# mp28164-buck-boost-flashlight-driver-17m.net
KiCad netlist of a schematic drawn in EAGLE
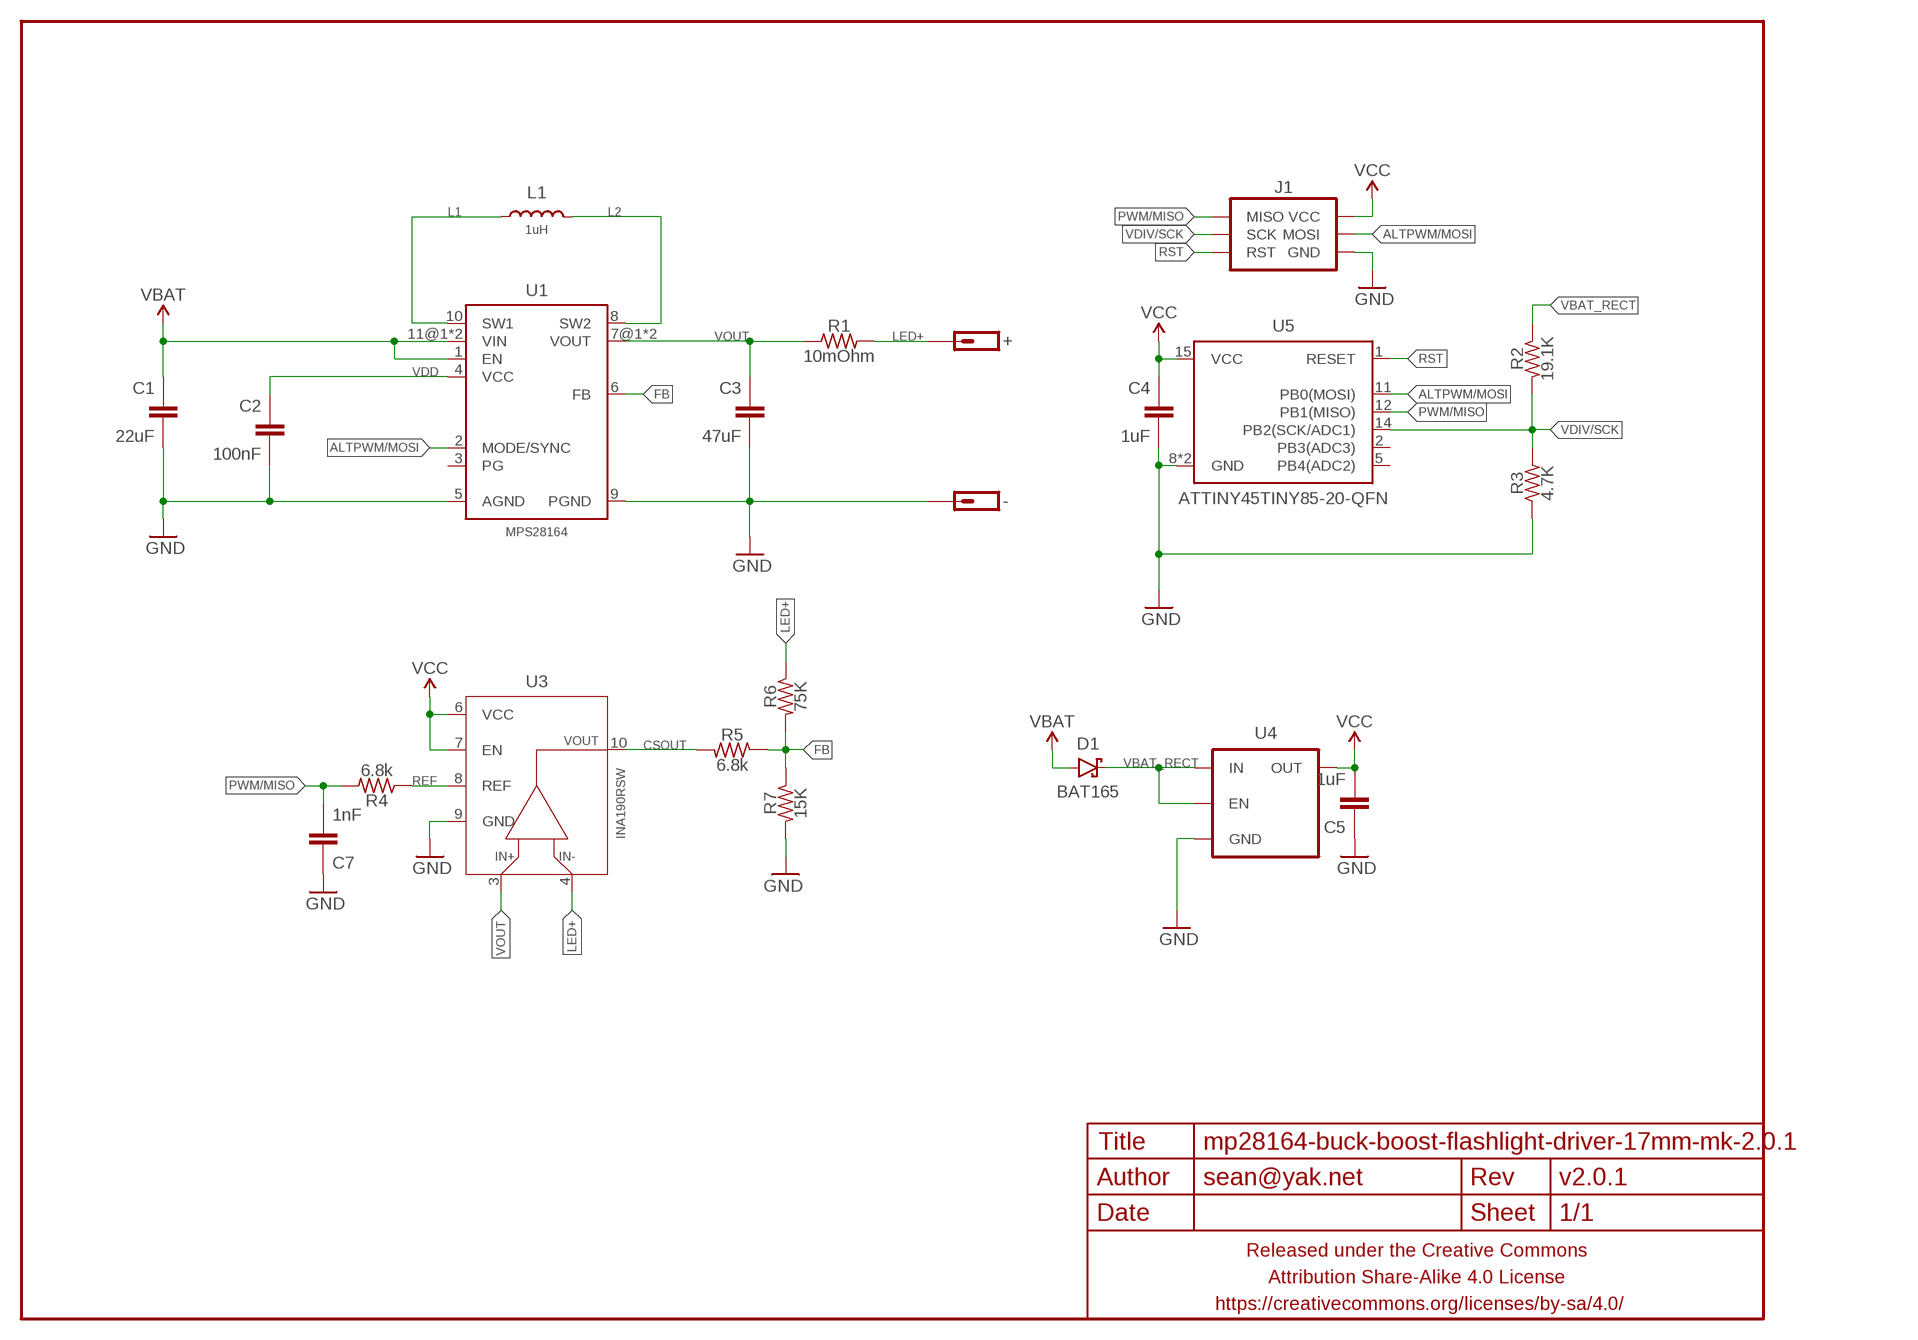
[diagram p0: schematic, sheet 1]

(export (version "E")
  (design (tool "Eeschema 10.0.6"))
  (components
    (comp (ref "+")
      (value "M01SMD-1.6MMX3.2MM-NS")
      (footprint "eagle-import:1X01-SMD-1.6MMX3.2MM-NS")
      (libsource (lib "eagle-import") (part "M01SMD-1.6MMX3.2MM-NS"))
    )
    (comp (ref "-")
      (value "M01SMD-1.6MMX3.2MM-NS")
      (footprint "eagle-import:1X01-SMD-1.6MMX3.2MM-NS")
      (libsource (lib "eagle-import") (part "M01SMD-1.6MMX3.2MM-NS"))
    )
    (comp (ref "C1")
      (value "22uF")
      (footprint "eagle-import:C1206")
      (libsource (lib "eagle-import") (part "CAPACITOR-CERAMICC1206"))
    )
    (comp (ref "C2")
      (value "100nF")
      (footprint "eagle-import:C0402")
      (libsource (lib "eagle-import") (part "CAPACITOR-CERAMICC0402"))
    )
    (comp (ref "C3")
      (value "47uF")
      (footprint "eagle-import:C1206")
      (libsource (lib "eagle-import") (part "CAPACITOR-CERAMICC1206"))
    )
    (comp (ref "C4")
      (value "1uF")
      (footprint "eagle-import:C0402")
      (libsource (lib "eagle-import") (part "CAPACITOR-CERAMICC0402"))
    )
    (comp (ref "C5")
      (value "1uF")
      (footprint "eagle-import:C0402")
      (libsource (lib "eagle-import") (part "CAPACITOR-CERAMICC0402"))
    )
    (comp (ref "C7")
      (value "1nF")
      (footprint "eagle-import:C0402")
      (libsource (lib "eagle-import") (part "CAPACITOR-CERAMICC0402"))
    )
    (comp (ref "D1")
      (value "BAT165")
      (footprint "eagle-import:SOD323-SCHOTTKY")
      (libsource (lib "eagle-import") (part "DIODE-SCHOTTKYSOD323"))
    )
    (comp (ref "FRAME1")
      (value "FRAME-LETTERNO_PACKAGE")
      (footprint "eagle-import:DUMMY")
      (fields
        (field (name "DESIGNER") "sean@yak.net")
        (field (name "VERSION") "v2.0.1")
        (field (name "DESIGNER_1") "sean@yak.net")
        (field (name "VERSION_1") "v2.0.1")
      )
      (libsource (lib "eagle-import") (part "FRAME-LETTERNO_PACKAGE"))
    )
    (comp (ref "J1")
      (value "AVR_SPI_PRG_6SMD-1.27MM")
      (footprint "eagle-import:2X3-1.27MM-SMD")
      (libsource (lib "eagle-import") (part "AVR_SPI_PRG_6SMD-1.27MM"))
    )
    (comp (ref "L1")
      (value "1uH")
      (footprint "eagle-import:XAL7070")
      (libsource (lib "eagle-import") (part "INDUCTORXAL7070"))
    )
    (comp (ref "R1")
      (value "10mOhm")
      (footprint "eagle-import:R1206")
      (libsource (lib "eagle-import") (part "RESISTORR1206"))
    )
    (comp (ref "R2")
      (value "19.1K")
      (footprint "eagle-import:R0402")
      (libsource (lib "eagle-import") (part "RESISTORR0402"))
    )
    (comp (ref "R3")
      (value "4.7K")
      (footprint "eagle-import:R0402")
      (libsource (lib "eagle-import") (part "RESISTORR0402"))
    )
    (comp (ref "R4")
      (value "6.8k")
      (footprint "eagle-import:R0402")
      (libsource (lib "eagle-import") (part "RESISTORR0402"))
    )
    (comp (ref "R5")
      (value "6.8k")
      (footprint "eagle-import:R0402")
      (libsource (lib "eagle-import") (part "RESISTORR0402"))
    )
    (comp (ref "R6")
      (value "75K")
      (footprint "eagle-import:R0402")
      (libsource (lib "eagle-import") (part "RESISTORR0402"))
    )
    (comp (ref "R7")
      (value "15K")
      (footprint "eagle-import:R0402")
      (libsource (lib "eagle-import") (part "RESISTORR0402"))
    )
    (comp (ref "U1")
      (value "MPS28164")
      (footprint "eagle-import:MPS28164")
      (libsource (lib "eagle-import") (part "MPS28164"))
    )
    (comp (ref "U3")
      (value "INA190RSW")
      (footprint "eagle-import:UQFN-10")
      (libsource (lib "eagle-import") (part "INA190RSW"))
    )
    (comp (ref "U4")
      (value "V_REG_ENTLV700")
      (footprint "eagle-import:SC70")
      (libsource (lib "eagle-import") (part "V_REG_ENTLV700"))
    )
    (comp (ref "U5")
      (value "ATTINY45TINY85-20-QFN")
      (footprint "eagle-import:QFN20")
      (libsource (lib "eagle-import") (part "ATTINY45TINY85-20-QFN"))
    )
  )
  (nets
    (net (code "1") (name "/CSOUT") (class "Default")
      (node (ref "R5") (pin "2") (pinfunction "2_2") (pintype "passive"))
      (node (ref "U3") (pin "10") (pinfunction "OUT_10") (pintype "bidirectional"))
    )
    (net (code "2") (name "/L1") (class "Default")
      (node (ref "L1") (pin "P$1") (pinfunction "1_P$1") (pintype "passive"))
      (node (ref "U1") (pin "10") (pinfunction "SW1_10") (pintype "bidirectional"))
    )
    (net (code "3") (name "/L2") (class "Default")
      (node (ref "L1") (pin "P$2") (pinfunction "2_P$2") (pintype "passive"))
      (node (ref "U1") (pin "8") (pinfunction "SW2_8") (pintype "bidirectional"))
    )
    (net (code "4") (name "/REF") (class "Default")
      (node (ref "R4") (pin "1") (pinfunction "1_1") (pintype "passive"))
      (node (ref "U3") (pin "8") (pinfunction "REF_8") (pintype "bidirectional"))
    )
    (net (code "5") (name "/VDD") (class "Default")
      (node (ref "C2") (pin "1") (pinfunction "1_1") (pintype "passive"))
      (node (ref "U1") (pin "4") (pinfunction "VCC_4") (pintype "bidirectional"))
    )
    (net (code "6") (name "ALTPWM{slash}MOSI") (class "Default")
      (node (ref "J1") (pin "4") (pinfunction "MOSI_4") (pintype "passive"))
      (node (ref "U1") (pin "2") (pinfunction "MODE/SYNC_2") (pintype "bidirectional"))
      (node (ref "U5") (pin "11") (pinfunction "PB0(MOSI)_11") (pintype "bidirectional"))
    )
    (net (code "7") (name "FB") (class "Default")
      (node (ref "R5") (pin "1") (pinfunction "1_1") (pintype "passive"))
      (node (ref "R6") (pin "2") (pinfunction "2_2") (pintype "passive"))
      (node (ref "R7") (pin "1") (pinfunction "1_1") (pintype "passive"))
      (node (ref "U1") (pin "6") (pinfunction "FB_6") (pintype "bidirectional"))
    )
    (net (code "8") (name "GND") (class "Default")
      (node (ref "-") (pin "P$1") (pinfunction "1_P$1") (pintype "passive"))
      (node (ref "C1") (pin "2") (pinfunction "2_2") (pintype "passive"))
      (node (ref "C2") (pin "2") (pinfunction "2_2") (pintype "passive"))
      (node (ref "C3") (pin "2") (pinfunction "2_2") (pintype "passive"))
      (node (ref "C4") (pin "2") (pinfunction "2_2") (pintype "passive"))
      (node (ref "C5") (pin "1") (pinfunction "1_1") (pintype "passive"))
      (node (ref "C7") (pin "1") (pinfunction "1_1") (pintype "passive"))
      (node (ref "J1") (pin "6") (pinfunction "GND_6") (pintype "passive"))
      (node (ref "R3") (pin "1") (pinfunction "1_1") (pintype "passive"))
      (node (ref "R7") (pin "2") (pinfunction "2_2") (pintype "passive"))
      (node (ref "U1") (pin "5") (pinfunction "AGND_5") (pintype "bidirectional"))
      (node (ref "U1") (pin "9") (pinfunction "PGND_9") (pintype "bidirectional"))
      (node (ref "U3") (pin "9") (pinfunction "GND_9") (pintype "bidirectional"))
      (node (ref "U4") (pin "2") (pinfunction "GND_2") (pintype "input"))
      (node (ref "U5") (pin "8") (pinfunction "GND_8") (pintype "bidirectional"))
      (node (ref "U5") (pin "PAD") (pinfunction "GND_PAD") (pintype "bidirectional"))
    )
    (net (code "9") (name "LED+") (class "Default")
      (node (ref "+") (pin "P$1") (pinfunction "1_P$1") (pintype "passive"))
      (node (ref "R1") (pin "2") (pinfunction "2_2") (pintype "passive"))
      (node (ref "R6") (pin "1") (pinfunction "1_1") (pintype "passive"))
      (node (ref "U3") (pin "4") (pinfunction "VIN-_4") (pintype "bidirectional"))
    )
    (net (code "10") (name "PWM{slash}MISO") (class "Default")
      (node (ref "C7") (pin "2") (pinfunction "2_2") (pintype "passive"))
      (node (ref "J1") (pin "1") (pinfunction "MISO_1") (pintype "passive"))
      (node (ref "R4") (pin "2") (pinfunction "2_2") (pintype "passive"))
      (node (ref "U5") (pin "12") (pinfunction "PB1(MISO)_12") (pintype "bidirectional"))
    )
    (net (code "11") (name "RST") (class "Default")
      (node (ref "J1") (pin "5") (pinfunction "RST_5") (pintype "passive"))
      (node (ref "U5") (pin "1") (pinfunction "RESET_1") (pintype "bidirectional"))
    )
    (net (code "12") (name "VBAT") (class "Default")
      (node (ref "C1") (pin "1") (pinfunction "1_1") (pintype "passive"))
      (node (ref "D1") (pin "A") (pinfunction "A_A") (pintype "passive"))
      (node (ref "U1") (pin "1") (pinfunction "EN_1") (pintype "bidirectional"))
      (node (ref "U1") (pin "11@1") (pinfunction "VIN_11@1") (pintype "bidirectional"))
      (node (ref "U1") (pin "11@2") (pinfunction "VIN_11@2") (pintype "bidirectional"))
    )
    (net (code "13") (name "VBAT_RECT") (class "Default")
      (node (ref "D1") (pin "C") (pinfunction "C_C") (pintype "passive"))
      (node (ref "R2") (pin "1") (pinfunction "1_1") (pintype "passive"))
      (node (ref "U4") (pin "1") (pinfunction "IN_1") (pintype "input"))
      (node (ref "U4") (pin "3") (pinfunction "EN_3") (pintype "input"))
    )
    (net (code "14") (name "VCC") (class "Default")
      (node (ref "C4") (pin "1") (pinfunction "1_1") (pintype "passive"))
      (node (ref "C5") (pin "2") (pinfunction "2_2") (pintype "passive"))
      (node (ref "J1") (pin "2") (pinfunction "VCC_2") (pintype "passive"))
      (node (ref "U3") (pin "6") (pinfunction "VCC_6") (pintype "bidirectional"))
      (node (ref "U3") (pin "7") (pinfunction "EN_7") (pintype "bidirectional"))
      (node (ref "U4") (pin "5") (pinfunction "OUT_5") (pintype "passive"))
      (node (ref "U5") (pin "15") (pinfunction "VCC_15") (pintype "bidirectional"))
    )
    (net (code "15") (name "VDIV{slash}SCK") (class "Default")
      (node (ref "J1") (pin "3") (pinfunction "SCK_3") (pintype "passive"))
      (node (ref "R2") (pin "2") (pinfunction "2_2") (pintype "passive"))
      (node (ref "R3") (pin "2") (pinfunction "2_2") (pintype "passive"))
      (node (ref "U5") (pin "14") (pinfunction "PB2(SCK/ADC1)_14") (pintype "bidirectional"))
    )
    (net (code "16") (name "VOUT") (class "Default")
      (node (ref "C3") (pin "1") (pinfunction "1_1") (pintype "passive"))
      (node (ref "R1") (pin "1") (pinfunction "1_1") (pintype "passive"))
      (node (ref "U1") (pin "7@1") (pinfunction "VOUT_7@1") (pintype "bidirectional"))
      (node (ref "U1") (pin "7@2") (pinfunction "VOUT_7@2") (pintype "bidirectional"))
      (node (ref "U3") (pin "3") (pinfunction "VIN+_3") (pintype "bidirectional"))
    )
    (net (code "17") (name "unconnected-(U1-PG-Pad3)") (class "Default")
      (node (ref "U1") (pin "3") (pinfunction "PG_3") (pintype "bidirectional"))
    )
    (net (code "18") (name "unconnected-(U5-PB3(ADC3)-Pad2)") (class "Default")
      (node (ref "U5") (pin "2") (pinfunction "PB3(ADC3)_2") (pintype "bidirectional"))
    )
    (net (code "19") (name "unconnected-(U5-PB4(ADC2)-Pad5)") (class "Default")
      (node (ref "U5") (pin "5") (pinfunction "PB4(ADC2)_5") (pintype "bidirectional"))
    )
  )
)
